# bms_schematic.net
KiCad netlist of a schematic drawn in Altium Designer
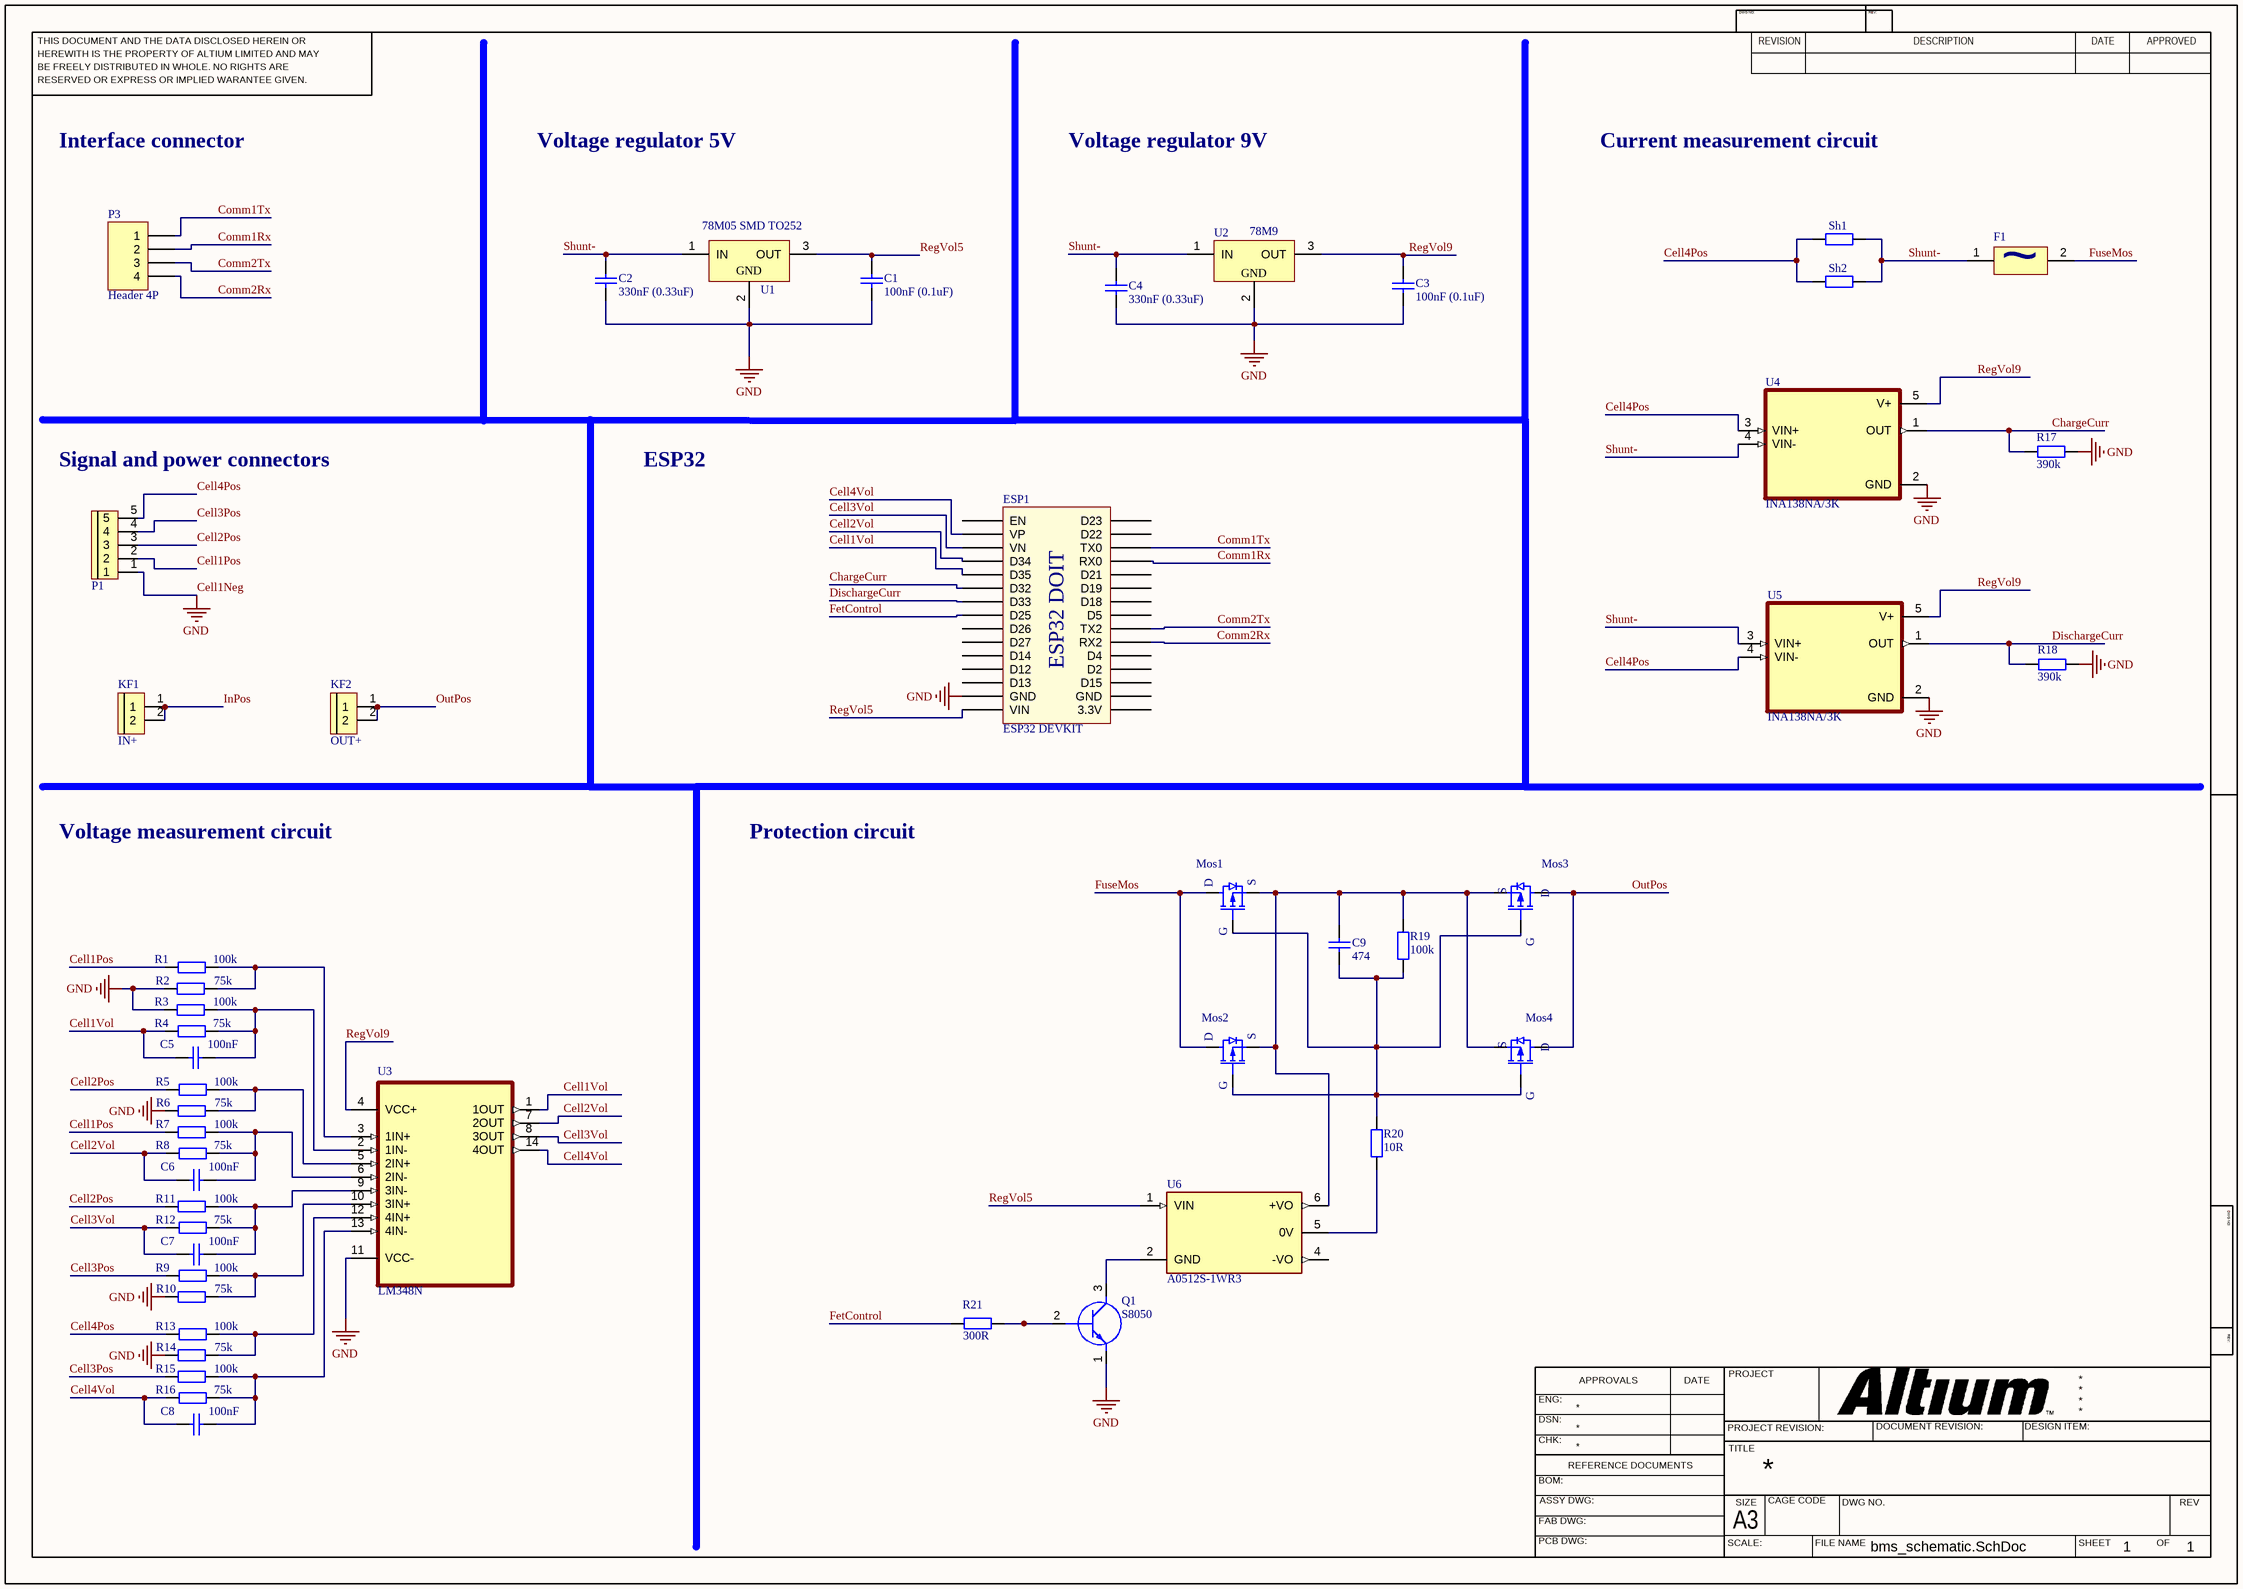
[diagram p0: bms_schematic.SchDoc]

(export (version "E")
  (design (tool "Eeschema 10.0.6"))
  (components
    (comp (ref "C1")
      (value "100nF (0.1uF)")
      (footprint "tu 0805")
      (description "Dán")
      (libsource (lib "Altium_Lib_by_KhueNguyenCreator") (part "Tu 0805 331 50V 10%"))
    )
    (comp (ref "C2")
      (value "330nF (0.33uF)")
      (footprint "tu 0805")
      (description "Dán")
      (libsource (lib "Altium_Lib_by_KhueNguyenCreator") (part "Tu 0805 331 50V 10%"))
    )
    (comp (ref "C3")
      (value "100nF (0.1uF)")
      (footprint "tu 0805")
      (description "Dán")
      (libsource (lib "Altium_Lib_by_KhueNguyenCreator") (part "Tu 0805 331 50V 10%"))
    )
    (comp (ref "C4")
      (value "330nF (0.33uF)")
      (footprint "tu 0805")
      (description "Dán")
      (libsource (lib "Altium_Lib_by_KhueNguyenCreator") (part "Tu 0805 331 50V 10%"))
    )
    (comp (ref "C5")
      (value "100nF")
      (footprint "tu 0805")
      (description "Dán")
      (libsource (lib "Altium_Lib_by_KhueNguyenCreator") (part "Tu 0805 331 50V 10%"))
    )
    (comp (ref "C6")
      (value "100nF")
      (footprint "tu 0805")
      (description "Dán")
      (libsource (lib "Altium_Lib_by_KhueNguyenCreator") (part "Tu 0805 331 50V 10%"))
    )
    (comp (ref "C7")
      (value "100nF")
      (footprint "tu 0805")
      (description "Dán")
      (libsource (lib "Altium_Lib_by_KhueNguyenCreator") (part "Tu 0805 331 50V 10%"))
    )
    (comp (ref "C8")
      (value "100nF")
      (footprint "tu 0805")
      (description "Dán")
      (libsource (lib "Altium_Lib_by_KhueNguyenCreator") (part "Tu 0805 331 50V 10%"))
    )
    (comp (ref "C9")
      (value "474")
      (footprint "tu 0805")
      (description "Dán")
      (libsource (lib "Altium_Lib_by_KhueNguyenCreator") (part "Tu 0805 474 50V 10%"))
    )
    (comp (ref "ESP1")
      (value "ESP32 DEVKIT")
      (footprint "ESP32 WROOM 32 KIT")
      (libsource (lib "Module1") (part "ESP32 WROOM 32 KIT"))
    )
    (comp (ref "F1")
      (value "~")
      (footprint "FUSE_3A_HOLDER")
      (description "PB wire fuse")
      (libsource (lib "02.Power-Protection") (part "FUSE_PbWire"))
    )
    (comp (ref "KF1")
      (value "IN+")
      (footprint "Con 2 KF301 5.08")
      (description "Cắm")
      (libsource (lib "Altium_Lib_by_KhueNguyenCreator") (part "CON 2 KF301"))
    )
    (comp (ref "KF2")
      (value "OUT+")
      (footprint "Con 2 KF301 5.08")
      (description "Cắm")
      (libsource (lib "Altium_Lib_by_KhueNguyenCreator") (part "CON 2 KF301"))
    )
    (comp (ref "Mos1")
      (value "AOD403")
      (footprint "TO-252-3")
      (libsource (lib "03.Semiconductor") (part "AOD403"))
    )
    (comp (ref "Mos2")
      (value "AOD403")
      (footprint "TO-252-3")
      (libsource (lib "03.Semiconductor") (part "AOD403"))
    )
    (comp (ref "Mos3")
      (value "AOD403")
      (footprint "TO-252-3")
      (libsource (lib "03.Semiconductor") (part "AOD403"))
    )
    (comp (ref "Mos4")
      (value "AOD403")
      (footprint "TO-252-3")
      (libsource (lib "03.Semiconductor") (part "AOD403"))
    )
    (comp (ref "P1")
      (value "CON 5 EDG5.08")
      (footprint "CON 5 5EDG5.08")
      (description "Cắm")
      (libsource (lib "Altium_Lib_by_KhueNguyenCreator") (part "CON 5 EDG5.08"))
    )
    (comp (ref "P3")
      (value "Header 4P")
      (footprint "HDR1X4")
      (description "Header, 4 Pin Pitch 2.54mm")
      (fields (field (name "MPN") "S1012EC-40-ND"))
      (libsource (lib "04.Header-Connecter") (part "Header 4x1"))
    )
    (comp (ref "Q1")
      (value "S8050")
      (footprint "SamacSys:S8050")
      (description "Transistor BJT NPN")
      (libsource (lib "SamacSys") (part "S8050"))
    )
    (comp (ref "R1")
      (value "100k")
      (footprint "tro smd 0805")
      (description "Dán")
      (libsource (lib "Altium_Lib_by_KhueNguyenCreator") (part "Tro 0805 5% 100k"))
    )
    (comp (ref "R2")
      (value "75k")
      (footprint "tro SMD 0805")
      (description "Dán")
      (libsource (lib "Altium_Lib_by_KhueNguyenCreator") (part "Tro 0805 5% 75k"))
    )
    (comp (ref "R3")
      (value "100k")
      (footprint "tro smd 0805")
      (description "Dán")
      (libsource (lib "Altium_Lib_by_KhueNguyenCreator") (part "Tro 0805 5% 100k"))
    )
    (comp (ref "R4")
      (value "75k")
      (footprint "tro SMD 0805")
      (description "Dán")
      (libsource (lib "Altium_Lib_by_KhueNguyenCreator") (part "Tro 0805 5% 75k"))
    )
    (comp (ref "R5")
      (value "100k")
      (footprint "tro smd 0805")
      (description "Dán")
      (libsource (lib "Altium_Lib_by_KhueNguyenCreator") (part "Tro 0805 5% 100k"))
    )
    (comp (ref "R6")
      (value "75k")
      (footprint "tro SMD 0805")
      (description "Dán")
      (libsource (lib "Altium_Lib_by_KhueNguyenCreator") (part "Tro 0805 5% 75k"))
    )
    (comp (ref "R7")
      (value "100k")
      (footprint "tro smd 0805")
      (description "Dán")
      (libsource (lib "Altium_Lib_by_KhueNguyenCreator") (part "Tro 0805 5% 100k"))
    )
    (comp (ref "R8")
      (value "75k")
      (footprint "tro SMD 0805")
      (description "Dán")
      (libsource (lib "Altium_Lib_by_KhueNguyenCreator") (part "Tro 0805 5% 75k"))
    )
    (comp (ref "R9")
      (value "100k")
      (footprint "tro smd 0805")
      (description "Dán")
      (libsource (lib "Altium_Lib_by_KhueNguyenCreator") (part "Tro 0805 5% 100k"))
    )
    (comp (ref "R10")
      (value "75k")
      (footprint "tro SMD 0805")
      (description "Dán")
      (libsource (lib "Altium_Lib_by_KhueNguyenCreator") (part "Tro 0805 5% 75k"))
    )
    (comp (ref "R11")
      (value "100k")
      (footprint "tro smd 0805")
      (description "Dán")
      (libsource (lib "Altium_Lib_by_KhueNguyenCreator") (part "Tro 0805 5% 100k"))
    )
    (comp (ref "R12")
      (value "75k")
      (footprint "tro SMD 0805")
      (description "Dán")
      (libsource (lib "Altium_Lib_by_KhueNguyenCreator") (part "Tro 0805 5% 75k"))
    )
    (comp (ref "R13")
      (value "100k")
      (footprint "tro smd 0805")
      (description "Dán")
      (libsource (lib "Altium_Lib_by_KhueNguyenCreator") (part "Tro 0805 5% 100k"))
    )
    (comp (ref "R14")
      (value "75k")
      (footprint "tro SMD 0805")
      (description "Dán")
      (libsource (lib "Altium_Lib_by_KhueNguyenCreator") (part "Tro 0805 5% 75k"))
    )
    (comp (ref "R15")
      (value "100k")
      (footprint "tro smd 0805")
      (description "Dán")
      (libsource (lib "Altium_Lib_by_KhueNguyenCreator") (part "Tro 0805 5% 100k"))
    )
    (comp (ref "R16")
      (value "75k")
      (footprint "tro SMD 0805")
      (description "Dán")
      (libsource (lib "Altium_Lib_by_KhueNguyenCreator") (part "Tro 0805 5% 75k"))
    )
    (comp (ref "R17")
      (value "390k")
      (footprint "Tro SMD 0805")
      (description "Dán")
      (libsource (lib "Altium_Lib_by_KhueNguyenCreator") (part "Tro 0805 5% 390k"))
    )
    (comp (ref "R18")
      (value "390k")
      (footprint "Tro SMD 0805")
      (description "Dán")
      (libsource (lib "Altium_Lib_by_KhueNguyenCreator") (part "Tro 0805 5% 390k"))
    )
    (comp (ref "R19")
      (value "100k")
      (footprint "tro smd 0805")
      (description "Dán")
      (libsource (lib "Altium_Lib_by_KhueNguyenCreator") (part "Tro 0805 5% 100k"))
    )
    (comp (ref "R20")
      (value "10R")
      (footprint "tro smd 0805")
      (description "Dán")
      (libsource (lib "Altium_Lib_by_KhueNguyenCreator") (part "Tro 0805 5% 10R"))
    )
    (comp (ref "R21")
      (value "300R")
      (footprint "Tro SMD 0805")
      (description "Dán")
      (libsource (lib "Altium_Lib_by_KhueNguyenCreator") (part "Tro 0805 5% 300R"))
    )
    (comp (ref "Sh1") (value "Shunt") (footprint "Shunt") (libsource (lib "01.Passives") (part "Shunt")))
    (comp (ref "Sh2") (value "Shunt") (footprint "Shunt") (libsource (lib "01.Passives") (part "Shunt")))
    (comp (ref "U1")
      (value "78M05 SMD TO252")
      (footprint "TO252")
      (description "Dán")
      (libsource (lib "Altium_Lib_by_KhueNguyenCreator") (part "78M05 SMD TO252"))
    )
    (comp (ref "U2")
      (value "78M9")
      (footprint "TO252")
      (description "Dán")
      (libsource (lib "Altium_Lib_by_KhueNguyenCreator") (part "78M09 SMD TO252"))
    )
    (comp (ref "U3")
      (value "LM348N")
      (footprint "DIP254P762X508-14")
      (description "General Purpose Amplifier 4 Circuit 14-DIP")
      (fields (field (name "MF") "STMicroelectronics"))
      (libsource (lib "LM348N") (part "LM348N"))
    )
    (comp (ref "U4")
      (value "INA138NA/3K")
      (footprint "SOT95P280X145-5N")
      (description "2.7 to 36V, 800kHz Variable gain current sense amplifier 5-SOT-23 -40 to 125")
      (fields
        (field (name "MF") "Texas Instruments")
        (field (name "BUYPART") "https://www.snapeda.com/parts/INA138NA/3K/Texas%20Instruments/view-part/11314/?ref=eda")
      )
      (libsource (lib "INA138NA_3K") (part "INA138NA/3K"))
    )
    (comp (ref "U5")
      (value "INA138NA/3K")
      (footprint "SOT95P280X145-5N")
      (description "2.7 to 36V, 800kHz Variable gain current sense amplifier 5-SOT-23 -40 to 125")
      (fields
        (field (name "MF") "Texas Instruments")
        (field (name "BUYPART") "https://www.snapeda.com/parts/INA138NA/3K/Texas%20Instruments/view-part/11314/?ref=eda")
      )
      (libsource (lib "INA138NA_3K") (part "INA138NA/3K"))
    )
    (comp (ref "U6")
      (value "A0512S-1WR3")
      (footprint "CONV_A0512S-1WR3")
      (description "Isolated Module DC DC Converter 2 Output 12V -12V 42mA, 42mA 4.5V - 5.5V Input")
      (fields (field (name "MF") "Mornsun America, LLC"))
      (libsource (lib "A0512S-1WR3") (part "A0512S-1WR3"))
    )
  )
  (nets
    (net (code "1") (name "/Cell1Pos") (class "Default")
      (node (ref "P1") (pin "2") (pinfunction "2_2") (pintype "passive"))
      (node (ref "R1") (pin "1") (pinfunction "1_1") (pintype "passive"))
      (node (ref "R7") (pin "1") (pinfunction "1_1") (pintype "passive"))
    )
    (net (code "2") (name "/Cell1Vol") (class "Default")
      (node (ref "C5") (pin "1") (pinfunction "1_1") (pintype "passive"))
      (node (ref "ESP1") (pin "5") (pinfunction "D35_5") (pintype "passive"))
      (node (ref "R4") (pin "1") (pinfunction "1_1") (pintype "passive"))
      (node (ref "U3") (pin "1") (pinfunction "1OUT_1") (pintype "output"))
    )
    (net (code "3") (name "/Cell2Pos") (class "Default")
      (node (ref "P1") (pin "3") (pinfunction "3_3") (pintype "passive"))
      (node (ref "R11") (pin "1") (pinfunction "1_1") (pintype "passive"))
      (node (ref "R5") (pin "1") (pinfunction "1_1") (pintype "passive"))
    )
    (net (code "4") (name "/Cell2Vol") (class "Default")
      (node (ref "C6") (pin "1") (pinfunction "1_1") (pintype "passive"))
      (node (ref "ESP1") (pin "4") (pinfunction "D34_4") (pintype "passive"))
      (node (ref "R8") (pin "1") (pinfunction "1_1") (pintype "passive"))
      (node (ref "U3") (pin "7") (pinfunction "2OUT_7") (pintype "output"))
    )
    (net (code "5") (name "/Cell3Pos") (class "Default")
      (node (ref "P1") (pin "4") (pinfunction "4_4") (pintype "passive"))
      (node (ref "R15") (pin "1") (pinfunction "1_1") (pintype "passive"))
      (node (ref "R9") (pin "1") (pinfunction "1_1") (pintype "passive"))
    )
    (net (code "6") (name "/Cell3Vol") (class "Default")
      (node (ref "C7") (pin "1") (pinfunction "1_1") (pintype "passive"))
      (node (ref "ESP1") (pin "3") (pinfunction "VN_3") (pintype "passive"))
      (node (ref "R12") (pin "1") (pinfunction "1_1") (pintype "passive"))
      (node (ref "U3") (pin "8") (pinfunction "3OUT_8") (pintype "output"))
    )
    (net (code "7") (name "/Cell4Pos") (class "Default")
      (node (ref "P1") (pin "5") (pinfunction "5_5") (pintype "passive"))
      (node (ref "R13") (pin "1") (pinfunction "1_1") (pintype "passive"))
      (node (ref "Sh1") (pin "1") (pinfunction "1_1") (pintype "passive"))
      (node (ref "Sh2") (pin "1") (pinfunction "1_1") (pintype "passive"))
      (node (ref "U4") (pin "3") (pinfunction "VIN+_3") (pintype "input"))
      (node (ref "U5") (pin "4") (pinfunction "VIN-_4") (pintype "input"))
    )
    (net (code "8") (name "/Cell4Vol") (class "Default")
      (node (ref "C8") (pin "1") (pinfunction "1_1") (pintype "passive"))
      (node (ref "ESP1") (pin "2") (pinfunction "VP_2") (pintype "passive"))
      (node (ref "R16") (pin "1") (pinfunction "1_1") (pintype "passive"))
      (node (ref "U3") (pin "14") (pinfunction "4OUT_14") (pintype "output"))
    )
    (net (code "9") (name "/ChargeCurr") (class "Default")
      (node (ref "ESP1") (pin "6") (pinfunction "D32_6") (pintype "passive"))
      (node (ref "R17") (pin "1") (pinfunction "1_1") (pintype "passive"))
      (node (ref "U4") (pin "1") (pinfunction "OUT_1") (pintype "output"))
    )
    (net (code "10") (name "/Comm1Rx") (class "Default")
      (node (ref "ESP1") (pin "27") (pinfunction "RX0_27") (pintype "passive"))
      (node (ref "P3") (pin "2") (pinfunction "2_2") (pintype "passive"))
    )
    (net (code "11") (name "/Comm1Tx") (class "Default")
      (node (ref "ESP1") (pin "28") (pinfunction "TX0_28") (pintype "passive"))
      (node (ref "P3") (pin "1") (pinfunction "1_1") (pintype "passive"))
    )
    (net (code "12") (name "/Comm2Rx") (class "Default")
      (node (ref "ESP1") (pin "21") (pinfunction "RX2_21") (pintype "passive"))
      (node (ref "P3") (pin "4") (pinfunction "4_4") (pintype "passive"))
    )
    (net (code "13") (name "/Comm2Tx") (class "Default")
      (node (ref "ESP1") (pin "22") (pinfunction "TX2_22") (pintype "passive"))
      (node (ref "P3") (pin "3") (pinfunction "3_3") (pintype "passive"))
    )
    (net (code "14") (name "/DischargeCurr") (class "Default")
      (node (ref "ESP1") (pin "7") (pinfunction "D33_7") (pintype "passive"))
      (node (ref "R18") (pin "1") (pinfunction "1_1") (pintype "passive"))
      (node (ref "U5") (pin "1") (pinfunction "OUT_1") (pintype "output"))
    )
    (net (code "15") (name "/FetControl") (class "Default")
      (node (ref "ESP1") (pin "8") (pinfunction "D25_8") (pintype "passive"))
      (node (ref "R21") (pin "1") (pinfunction "1_1") (pintype "passive"))
    )
    (net (code "16") (name "/FuseMos") (class "Default")
      (node (ref "F1") (pin "2") (pinfunction "2_2") (pintype "passive"))
      (node (ref "Mos1") (pin "2") (pinfunction "D_2") (pintype "passive"))
      (node (ref "Mos2") (pin "2") (pinfunction "D_2") (pintype "passive"))
    )
    (net (code "17") (name "/InPos") (class "Default")
      (node (ref "KF1") (pin "1") (pinfunction "1_1") (pintype "passive"))
      (node (ref "KF1") (pin "2") (pinfunction "2_2") (pintype "passive"))
    )
    (net (code "18") (name "/OutPos") (class "Default")
      (node (ref "KF2") (pin "1") (pinfunction "1_1") (pintype "passive"))
      (node (ref "KF2") (pin "2") (pinfunction "2_2") (pintype "passive"))
      (node (ref "Mos3") (pin "2") (pinfunction "D_2") (pintype "passive"))
      (node (ref "Mos4") (pin "2") (pinfunction "D_2") (pintype "passive"))
    )
    (net (code "19") (name "/RegVol5") (class "Default")
      (node (ref "C1") (pin "2") (pinfunction "2_2") (pintype "passive"))
      (node (ref "ESP1") (pin "15") (pinfunction "VIN_15") (pintype "passive"))
      (node (ref "U1") (pin "3") (pinfunction "OUT_3") (pintype "power_in"))
      (node (ref "U6") (pin "1") (pinfunction "VIN_1") (pintype "input"))
    )
    (net (code "20") (name "/RegVol9") (class "Default")
      (node (ref "C3") (pin "2") (pinfunction "2_2") (pintype "passive"))
      (node (ref "U2") (pin "3") (pinfunction "OUT_3") (pintype "power_in"))
      (node (ref "U3") (pin "4") (pinfunction "VCC+_4") (pintype "power_in"))
      (node (ref "U4") (pin "5") (pinfunction "V+_5") (pintype "power_in"))
      (node (ref "U5") (pin "5") (pinfunction "V+_5") (pintype "power_in"))
    )
    (net (code "21") (name "/Shunt-") (class "Default")
      (node (ref "C2") (pin "2") (pinfunction "2_2") (pintype "passive"))
      (node (ref "C4") (pin "2") (pinfunction "2_2") (pintype "passive"))
      (node (ref "F1") (pin "1") (pinfunction "1_1") (pintype "passive"))
      (node (ref "Sh1") (pin "2") (pinfunction "2_2") (pintype "passive"))
      (node (ref "Sh2") (pin "2") (pinfunction "2_2") (pintype "passive"))
      (node (ref "U1") (pin "1") (pinfunction "IN_1") (pintype "power_in"))
      (node (ref "U2") (pin "1") (pinfunction "IN_1") (pintype "power_in"))
      (node (ref "U4") (pin "4") (pinfunction "VIN-_4") (pintype "input"))
      (node (ref "U5") (pin "3") (pinfunction "VIN+_3") (pintype "input"))
    )
    (net (code "22") (name "GND") (class "Default")
      (node (ref "C1") (pin "1") (pinfunction "1_1") (pintype "passive"))
      (node (ref "C2") (pin "1") (pinfunction "1_1") (pintype "passive"))
      (node (ref "C3") (pin "1") (pinfunction "1_1") (pintype "passive"))
      (node (ref "C4") (pin "1") (pinfunction "1_1") (pintype "passive"))
      (node (ref "ESP1") (pin "14") (pinfunction "GND_14") (pintype "passive"))
      (node (ref "P1") (pin "1") (pinfunction "1_1") (pintype "passive"))
      (node (ref "Q1") (pin "1") (pinfunction "E_1") (pintype "passive"))
      (node (ref "R10") (pin "1") (pinfunction "1_1") (pintype "passive"))
      (node (ref "R14") (pin "1") (pinfunction "1_1") (pintype "passive"))
      (node (ref "R17") (pin "2") (pinfunction "2_2") (pintype "passive"))
      (node (ref "R18") (pin "2") (pinfunction "2_2") (pintype "passive"))
      (node (ref "R2") (pin "1") (pinfunction "1_1") (pintype "passive"))
      (node (ref "R3") (pin "1") (pinfunction "1_1") (pintype "passive"))
      (node (ref "R6") (pin "1") (pinfunction "1_1") (pintype "passive"))
      (node (ref "U1") (pin "2") (pinfunction "GND_2") (pintype "power_in"))
      (node (ref "U2") (pin "2") (pinfunction "GND_2") (pintype "power_in"))
      (node (ref "U3") (pin "11") (pinfunction "VCC-_11") (pintype "power_in"))
      (node (ref "U4") (pin "2") (pinfunction "GND_2") (pintype "power_in"))
      (node (ref "U5") (pin "2") (pinfunction "GND_2") (pintype "power_in"))
    )
    (net (code "23") (name "Net-(Mos1-G)") (class "Default")
      (node (ref "C9") (pin "2") (pinfunction "2_2") (pintype "passive"))
      (node (ref "Mos1") (pin "1") (pinfunction "G_1") (pintype "passive"))
      (node (ref "Mos2") (pin "1") (pinfunction "G_1") (pintype "passive"))
      (node (ref "Mos3") (pin "1") (pinfunction "G_1") (pintype "passive"))
      (node (ref "Mos4") (pin "1") (pinfunction "G_1") (pintype "passive"))
      (node (ref "R19") (pin "1") (pinfunction "1_1") (pintype "passive"))
      (node (ref "R20") (pin "2") (pinfunction "2_2") (pintype "passive"))
    )
    (net (code "24") (name "Net-(Mos1-S)") (class "Default")
      (node (ref "C9") (pin "1") (pinfunction "1_1") (pintype "passive"))
      (node (ref "Mos1") (pin "3") (pinfunction "S_3") (pintype "passive"))
      (node (ref "Mos2") (pin "3") (pinfunction "S_3") (pintype "passive"))
      (node (ref "Mos3") (pin "3") (pinfunction "S_3") (pintype "passive"))
      (node (ref "Mos4") (pin "3") (pinfunction "S_3") (pintype "passive"))
      (node (ref "R19") (pin "2") (pinfunction "2_2") (pintype "passive"))
      (node (ref "U6") (pin "6") (pinfunction "+VO_6") (pintype "output"))
    )
    (net (code "25") (name "Net-(Q1-B)") (class "Default")
      (node (ref "Q1") (pin "2") (pinfunction "B_2") (pintype "passive"))
      (node (ref "R21") (pin "2") (pinfunction "2_2") (pintype "passive"))
    )
    (net (code "26") (name "Net-(Q1-C)") (class "Default")
      (node (ref "Q1") (pin "3") (pinfunction "C_3") (pintype "passive"))
      (node (ref "U6") (pin "2") (pinfunction "GND_2") (pintype "power_in"))
    )
    (net (code "27") (name "Net-(U3-1IN+)") (class "Default")
      (node (ref "R1") (pin "2") (pinfunction "2_2") (pintype "passive"))
      (node (ref "R2") (pin "2") (pinfunction "2_2") (pintype "passive"))
      (node (ref "U3") (pin "3") (pinfunction "1IN+_3") (pintype "input"))
    )
    (net (code "28") (name "Net-(U3-1IN-)") (class "Default")
      (node (ref "C5") (pin "2") (pinfunction "2_2") (pintype "passive"))
      (node (ref "R3") (pin "2") (pinfunction "2_2") (pintype "passive"))
      (node (ref "R4") (pin "2") (pinfunction "2_2") (pintype "passive"))
      (node (ref "U3") (pin "2") (pinfunction "1IN-_2") (pintype "input"))
    )
    (net (code "29") (name "Net-(U3-2IN+)") (class "Default")
      (node (ref "R5") (pin "2") (pinfunction "2_2") (pintype "passive"))
      (node (ref "R6") (pin "2") (pinfunction "2_2") (pintype "passive"))
      (node (ref "U3") (pin "5") (pinfunction "2IN+_5") (pintype "input"))
    )
    (net (code "30") (name "Net-(U3-2IN-)") (class "Default")
      (node (ref "C6") (pin "2") (pinfunction "2_2") (pintype "passive"))
      (node (ref "R7") (pin "2") (pinfunction "2_2") (pintype "passive"))
      (node (ref "R8") (pin "2") (pinfunction "2_2") (pintype "passive"))
      (node (ref "U3") (pin "6") (pinfunction "2IN-_6") (pintype "input"))
    )
    (net (code "31") (name "Net-(U3-3IN+)") (class "Default")
      (node (ref "R10") (pin "2") (pinfunction "2_2") (pintype "passive"))
      (node (ref "R9") (pin "2") (pinfunction "2_2") (pintype "passive"))
      (node (ref "U3") (pin "10") (pinfunction "3IN+_10") (pintype "input"))
    )
    (net (code "32") (name "Net-(U3-3IN-)") (class "Default")
      (node (ref "C7") (pin "2") (pinfunction "2_2") (pintype "passive"))
      (node (ref "R11") (pin "2") (pinfunction "2_2") (pintype "passive"))
      (node (ref "R12") (pin "2") (pinfunction "2_2") (pintype "passive"))
      (node (ref "U3") (pin "9") (pinfunction "3IN-_9") (pintype "input"))
    )
    (net (code "33") (name "Net-(U3-4IN+)") (class "Default")
      (node (ref "R13") (pin "2") (pinfunction "2_2") (pintype "passive"))
      (node (ref "R14") (pin "2") (pinfunction "2_2") (pintype "passive"))
      (node (ref "U3") (pin "12") (pinfunction "4IN+_12") (pintype "input"))
    )
    (net (code "34") (name "Net-(U3-4IN-)") (class "Default")
      (node (ref "C8") (pin "2") (pinfunction "2_2") (pintype "passive"))
      (node (ref "R15") (pin "2") (pinfunction "2_2") (pintype "passive"))
      (node (ref "R16") (pin "2") (pinfunction "2_2") (pintype "passive"))
      (node (ref "U3") (pin "13") (pinfunction "4IN-_13") (pintype "input"))
    )
    (net (code "35") (name "Net-(U6-0V)") (class "Default")
      (node (ref "R20") (pin "1") (pinfunction "1_1") (pintype "passive"))
      (node (ref "U6") (pin "5") (pinfunction "0V_5") (pintype "passive"))
    )
    (net (code "36") (name "unconnected-(ESP1-3.3V-Pad16)") (class "Default")
      (node (ref "ESP1") (pin "16") (pinfunction "3.3V_16") (pintype "passive"))
    )
    (net (code "37") (name "unconnected-(ESP1-D2-Pad19)") (class "Default")
      (node (ref "ESP1") (pin "19") (pinfunction "D2_19") (pintype "passive"))
    )
    (net (code "38") (name "unconnected-(ESP1-D4-Pad20)") (class "Default")
      (node (ref "ESP1") (pin "20") (pinfunction "D4_20") (pintype "passive"))
    )
    (net (code "39") (name "unconnected-(ESP1-D5-Pad23)") (class "Default")
      (node (ref "ESP1") (pin "23") (pinfunction "D5_23") (pintype "passive"))
    )
    (net (code "40") (name "unconnected-(ESP1-D12-Pad12)") (class "Default")
      (node (ref "ESP1") (pin "12") (pinfunction "D12_12") (pintype "passive"))
    )
    (net (code "41") (name "unconnected-(ESP1-D13-Pad13)") (class "Default")
      (node (ref "ESP1") (pin "13") (pinfunction "D13_13") (pintype "passive"))
    )
    (net (code "42") (name "unconnected-(ESP1-D14-Pad11)") (class "Default")
      (node (ref "ESP1") (pin "11") (pinfunction "D14_11") (pintype "passive"))
    )
    (net (code "43") (name "unconnected-(ESP1-D15-Pad18)") (class "Default")
      (node (ref "ESP1") (pin "18") (pinfunction "D15_18") (pintype "passive"))
    )
    (net (code "44") (name "unconnected-(ESP1-D18-Pad24)") (class "Default")
      (node (ref "ESP1") (pin "24") (pinfunction "D18_24") (pintype "passive"))
    )
    (net (code "45") (name "unconnected-(ESP1-D19-Pad25)") (class "Default")
      (node (ref "ESP1") (pin "25") (pinfunction "D19_25") (pintype "passive"))
    )
    (net (code "46") (name "unconnected-(ESP1-D21-Pad26)") (class "Default")
      (node (ref "ESP1") (pin "26") (pinfunction "D21_26") (pintype "passive"))
    )
    (net (code "47") (name "unconnected-(ESP1-D22-Pad29)") (class "Default")
      (node (ref "ESP1") (pin "29") (pinfunction "D22_29") (pintype "passive"))
    )
    (net (code "48") (name "unconnected-(ESP1-D23-Pad30)") (class "Default")
      (node (ref "ESP1") (pin "30") (pinfunction "D23_30") (pintype "passive"))
    )
    (net (code "49") (name "unconnected-(ESP1-D26-Pad9)") (class "Default")
      (node (ref "ESP1") (pin "9") (pinfunction "D26_9") (pintype "passive"))
    )
    (net (code "50") (name "unconnected-(ESP1-D27-Pad10)") (class "Default")
      (node (ref "ESP1") (pin "10") (pinfunction "D27_10") (pintype "passive"))
    )
    (net (code "51") (name "unconnected-(ESP1-EN-Pad1)") (class "Default")
      (node (ref "ESP1") (pin "1") (pinfunction "EN_1") (pintype "passive"))
    )
    (net (code "52") (name "unconnected-(ESP1-GND-Pad17)") (class "Default")
      (node (ref "ESP1") (pin "17") (pinfunction "GND_17") (pintype "passive"))
    )
    (net (code "53") (name "unconnected-(U6--VO-Pad4)") (class "Default")
      (node (ref "U6") (pin "4") (pinfunction "-VO_4") (pintype "output"))
    )
  )
)
